# Boost_5V.net
KiCad netlist of a schematic drawn in Altium Designer
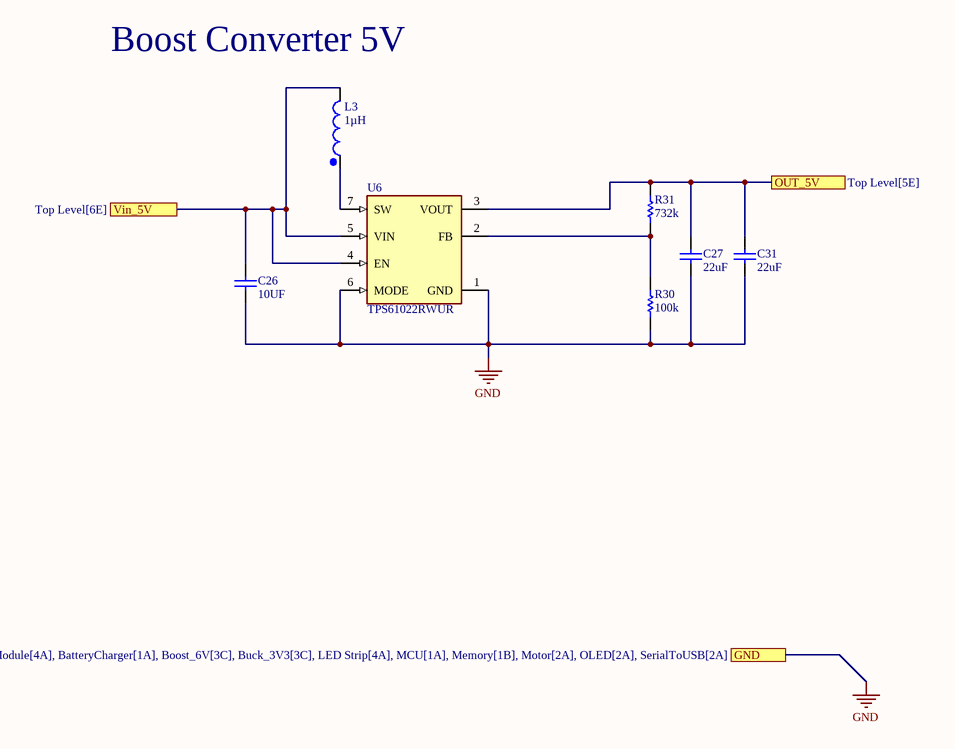
[diagram p0: Boost_5V.SchDoc]

(export (version "E")
  (design (tool "Eeschema 10.0.6"))
  (components
    (comp (ref "C26")
      (value "10UF")
      (footprint "0603_CAP")
      (description "Capacitor Surface Mount 0603 Footprint 10UF 16V 20% Tolerance Ceramic X5R")
      (fields (field (name "MANUFACTURER") "Various") (field (name "VOLTAGE") "16V"))
      (libsource (lib "University of Pennsylvania (ESE)") (part "cap"))
    )
    (comp (ref "C27")
      (value "22uF")
      (footprint "0805_CAP_60H")
      (description "Capacitor Surface Mount 0805 Footprint 22UF 10V 20% Tolerance Ceramic X5R")
      (fields (field (name "TOLERANCE") "20%") (field (name "MANUFACTURER") "Various"))
      (libsource (lib "University of Pennsylvania (ESE)") (part "cap"))
    )
    (comp (ref "C31")
      (value "22uF")
      (footprint "0805_CAP_60H")
      (description "Capacitor Surface Mount 0805 Footprint 22UF 10V 20% Tolerance Ceramic X5R")
      (fields (field (name "TOLERANCE") "20%") (field (name "MANUFACTURER") "Various"))
      (libsource (lib "University of Pennsylvania (ESE)") (part "cap"))
    )
    (comp (ref "L3")
      (value "1µH")
      (footprint "WE-HCI_7040")
      (description "General Purpose Inductor, 1uH, 20%, 1 Element, SMD, 2827")
      (fields (field (name "TOLERANCE") "20%") (field (name "Comment") "744311100"))
      (libsource (lib "University of Pennsylvania (ESE)") (part "INDUCTOR"))
    )
    (comp (ref "R30")
      (value "100k")
      (footprint "0805_RES")
      (description "Resistor Surface Mount, 100K Ohms, 0805 Footprint, 1% Tolerance 0.125W")
      (fields (field (name "MANUFACTURER") "Various") (field (name "TOLERANCE") "1%"))
      (libsource (lib "University of Pennsylvania (ESE)") (part "res"))
    )
    (comp (ref "R31")
      (value "732k")
      (footprint "0805_RES")
      (description "Resistor Surface Mount, 732K Ohms, 0805 Footprint, 1% Tolerance 0.125W")
      (fields (field (name "MANUFACTURER") "Various") (field (name "TOLERANCE") "1%"))
      (libsource (lib "University of Pennsylvania (ESE)") (part "res"))
    )
    (comp (ref "U6")
      (value "TPS61022RWUR")
      (footprint "FP-RWU0007A-MFG")
      (description "POWER MANAGEMENT")
      (fields
        (field (name "OCTOPART") "https://octopart.com/tps61022rwur-texas+instruments-100045592")
        (field (name "MANUFACTURER") "Texas Instruments")
      )
      (libsource (lib "Altium Content Vault") (part "f5e91e3b031270a67a8b4c367d09c5c"))
    )
  )
  (nets
    (net (code "1") (name "/OUT_5V") (class "Default")
      (node (ref "C27") (pin "2") (pinfunction "2_2") (pintype "passive"))
      (node (ref "C31") (pin "2") (pinfunction "2_2") (pintype "passive"))
      (node (ref "R31") (pin "2") (pinfunction "2_2") (pintype "passive"))
      (node (ref "U6") (pin "3") (pinfunction "VOUT_3") (pintype "power_in"))
    )
    (net (code "2") (name "/Vin_5V") (class "Default")
      (node (ref "C26") (pin "2") (pinfunction "2_2") (pintype "passive"))
      (node (ref "L3") (pin "2") (pinfunction "2_2") (pintype "passive"))
      (node (ref "U6") (pin "4") (pinfunction "EN_4") (pintype "input"))
      (node (ref "U6") (pin "5") (pinfunction "VIN_5") (pintype "input"))
    )
    (net (code "3") (name "GND") (class "Default")
      (node (ref "C26") (pin "1") (pinfunction "1_1") (pintype "passive"))
      (node (ref "C27") (pin "1") (pinfunction "1_1") (pintype "passive"))
      (node (ref "C31") (pin "1") (pinfunction "1_1") (pintype "passive"))
      (node (ref "R30") (pin "1") (pinfunction "1_1") (pintype "passive"))
      (node (ref "U6") (pin "1") (pinfunction "GND_1") (pintype "power_in"))
      (node (ref "U6") (pin "6") (pinfunction "MODE_6") (pintype "input"))
    )
    (net (code "4") (name "Net-(U6-FB)") (class "Default")
      (node (ref "R30") (pin "2") (pinfunction "2_2") (pintype "passive"))
      (node (ref "R31") (pin "1") (pinfunction "1_1") (pintype "passive"))
      (node (ref "U6") (pin "2") (pinfunction "FB_2") (pintype "power_in"))
    )
    (net (code "5") (name "Net-(U6-SW)") (class "Default")
      (node (ref "L3") (pin "1") (pinfunction "1_1") (pintype "passive"))
      (node (ref "U6") (pin "7") (pinfunction "SW_7") (pintype "input"))
    )
  )
)
